# CPU.net
KiCad netlist of a schematic drawn in Altium Designer
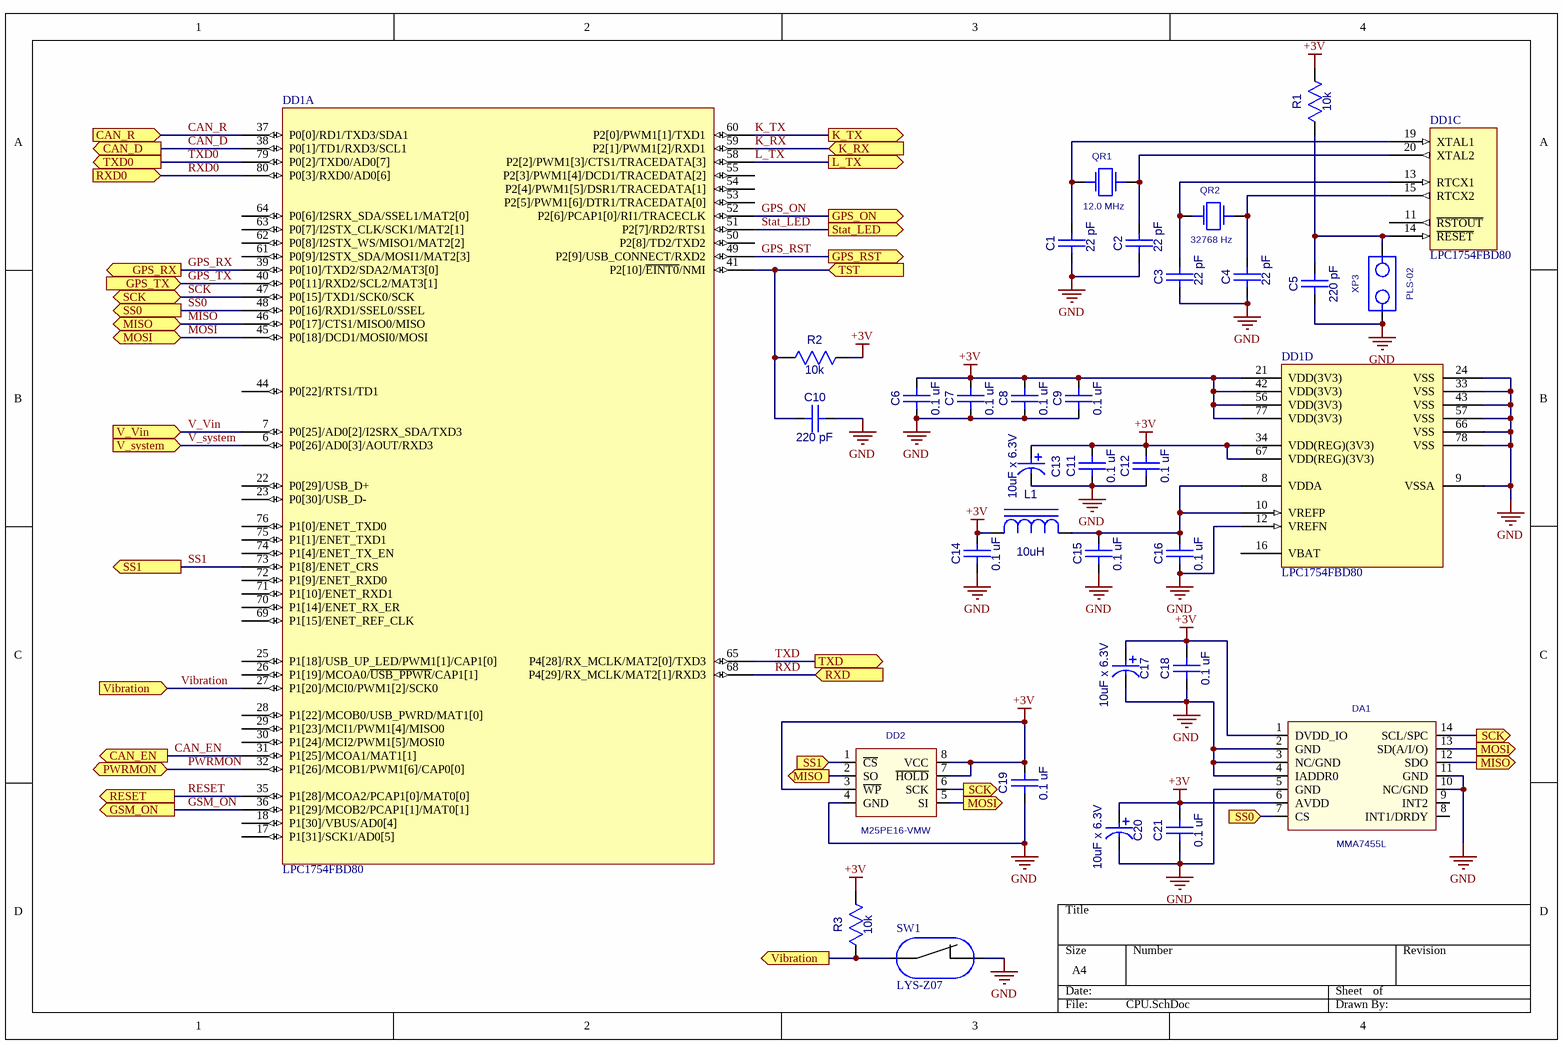
[diagram p0: CPU.SchDoc]

(export (version "E")
  (design (tool "Eeschema 10.0.6"))
  (components
    (comp (ref "C1")
      (value "22 pF")
      (footprint "CC0603-3M")
      (description "CC0603")
      (libsource (lib "gprs_modem") (part "CC0603"))
    )
    (comp (ref "C2")
      (value "22 pF")
      (footprint "CC0603-3M")
      (description "CC0603")
      (libsource (lib "gprs_modem") (part "CC0603"))
    )
    (comp (ref "C3")
      (value "22 pF")
      (footprint "CC0603-3M")
      (description "CC0603")
      (libsource (lib "gprs_modem") (part "CC0603"))
    )
    (comp (ref "C4")
      (value "22 pF")
      (footprint "CC0603-3M")
      (description "CC0603")
      (libsource (lib "gprs_modem") (part "CC0603"))
    )
    (comp (ref "C5")
      (value "220 pF")
      (footprint "CC0603-3M")
      (description "CC0603")
      (libsource (lib "gprs_modem") (part "CC0603"))
    )
    (comp (ref "C6")
      (value "0.1 uF")
      (footprint "CC0603-3M")
      (description "CC0603")
      (libsource (lib "gprs_modem") (part "CC0603"))
    )
    (comp (ref "C7")
      (value "0.1 uF")
      (footprint "CC0603-3M")
      (description "CC0603")
      (libsource (lib "gprs_modem") (part "CC0603"))
    )
    (comp (ref "C8")
      (value "0.1 uF")
      (footprint "CC0603-3M")
      (description "CC0603")
      (libsource (lib "gprs_modem") (part "CC0603"))
    )
    (comp (ref "C9")
      (value "0.1 uF")
      (footprint "CC0603-3M")
      (description "CC0603")
      (libsource (lib "gprs_modem") (part "CC0603"))
    )
    (comp (ref "C10")
      (value "220 pF")
      (footprint "CC0603-3M")
      (description "CC0603")
      (libsource (lib "gprs_modem") (part "CC0603"))
    )
    (comp (ref "C11")
      (value "0.1 uF")
      (footprint "CC0603-3M")
      (description "CC0603")
      (libsource (lib "gprs_modem") (part "CC0603"))
    )
    (comp (ref "C12")
      (value "0.1 uF")
      (footprint "CC0603-3M")
      (description "CC0603")
      (libsource (lib "gprs_modem") (part "CC0603"))
    )
    (comp (ref "C13")
      (value "10uF x 6.3V")
      (footprint "TAJ-A_M")
      (description "TAJ-A")
      (libsource (lib "Schetchik") (part "TAJ-A"))
    )
    (comp (ref "C14")
      (value "0.1 uF")
      (footprint "CC0603-3M")
      (description "CC0603")
      (libsource (lib "gprs_modem") (part "CC0603"))
    )
    (comp (ref "C15")
      (value "0.1 uF")
      (footprint "CC0603-3M")
      (description "CC0603")
      (libsource (lib "gprs_modem") (part "CC0603"))
    )
    (comp (ref "C16")
      (value "0.1 uF")
      (footprint "CC0603-3M")
      (description "CC0603")
      (libsource (lib "gprs_modem") (part "CC0603"))
    )
    (comp (ref "C17")
      (value "10uF x 6.3V")
      (footprint "TAJ-A_M")
      (description "TAJ-A")
      (libsource (lib "*") (part "TAJ-A"))
    )
    (comp (ref "C18")
      (value "0.1 uF")
      (footprint "CC0603-3M")
      (description "CC0603")
      (libsource (lib "*") (part "CC0603"))
    )
    (comp (ref "C19")
      (value "0.1 uF")
      (footprint "CC0603-3M")
      (description "CC0603")
      (libsource (lib "*") (part "CC0603"))
    )
    (comp (ref "C20")
      (value "10uF x 6.3V")
      (footprint "TAJ-A_M")
      (description "TAJ-A")
      (libsource (lib "*") (part "TAJ-A"))
    )
    (comp (ref "C21")
      (value "0.1 uF")
      (footprint "CC0603-3M")
      (description "CC0603")
      (libsource (lib "*") (part "CC0603"))
    )
    (comp (ref "DA1") (value "MMA7455L") (footprint "LGA-14") (libsource (lib "*") (part "MMA7455L")))
    (comp (ref "DD1")
      (value "LPC1754FBD80")
      (footprint "TQFP-80_0.5")
      (description "Cortex -M3 32-Bit Microcontroller, 128KB Flash, 64KB RAM, 800-Lead LQFP")
      (libsource (lib "gprs_modem") (part "LPC1754FBD80"))
    )
    (comp (ref "DD2")
      (value "M25PE16-VMW")
      (footprint "EIAJ_SO8")
      (description "S25FL016A0LMFI01")
      (libsource (lib "*") (part "S25FL016A0LMFI01"))
    )
    (comp (ref "L1")
      (value "10uH")
      (footprint "L0603")
      (description "L0603")
      (libsource (lib "gprs_modem") (part "L0603"))
    )
    (comp (ref "QR1")
      (value "12.0 MHz")
      (footprint "AC5032_2")
      (description "AC5032/2")
      (libsource (lib "gprs_modem") (part "AC5032_2"))
    )
    (comp (ref "QR2")
      (value "32768 Hz")
      (footprint "QR_32768")
      (description "CRYSTAL_32768 Hz")
      (libsource (lib "Schetchik") (part "CRYSTAL_32768"))
    )
    (comp (ref "R1")
      (value "10k")
      (footprint "RC0603-3M")
      (description "RC0603")
      (libsource (lib "gprs_modem") (part "RC0603"))
    )
    (comp (ref "R2")
      (value "10k")
      (footprint "RC0603-3M")
      (description "RC0603")
      (libsource (lib "gprs_modem") (part "RC0603"))
    )
    (comp (ref "R3")
      (value "10k")
      (footprint "RC0603-3M")
      (description "RC0603")
      (libsource (lib "gprs_modem") (part "RC0603"))
    )
    (comp (ref "SW1")
      (value "LYS-Z07")
      (footprint "LYS-Z07")
      (description "NC vibration sensor")
      (libsource (lib "gprs_modem") (part "LYS-Z07"))
    )
    (comp (ref "XP3") (value "PLS-02") (footprint "PIN2W") (libsource (lib "gprs_modem") (part "PLD-02")))
  )
  (nets
    (net (code "1") (name "+3V") (class "Default")
      (node (ref "C11") (pin "2") (pinfunction "B_2") (pintype "passive"))
      (node (ref "C12") (pin "2") (pinfunction "B_2") (pintype "passive"))
      (node (ref "C13") (pin "1") (pinfunction "A_1") (pintype "passive"))
      (node (ref "C14") (pin "2") (pinfunction "B_2") (pintype "passive"))
      (node (ref "C17") (pin "1") (pinfunction "A_1") (pintype "passive"))
      (node (ref "C18") (pin "2") (pinfunction "B_2") (pintype "passive"))
      (node (ref "C19") (pin "2") (pinfunction "B_2") (pintype "passive"))
      (node (ref "C20") (pin "1") (pinfunction "A_1") (pintype "passive"))
      (node (ref "C21") (pin "2") (pinfunction "B_2") (pintype "passive"))
      (node (ref "C6") (pin "2") (pinfunction "B_2") (pintype "passive"))
      (node (ref "C7") (pin "2") (pinfunction "B_2") (pintype "passive"))
      (node (ref "C8") (pin "2") (pinfunction "B_2") (pintype "passive"))
      (node (ref "C9") (pin "2") (pinfunction "B_2") (pintype "passive"))
      (node (ref "DA1") (pin "1") (pinfunction "DVDD_IO_1") (pintype "passive"))
      (node (ref "DA1") (pin "6") (pinfunction "AVDD_6") (pintype "passive"))
      (node (ref "DD1") (pin "21") (pinfunction "VDD(3V3)_21") (pintype "power_in"))
      (node (ref "DD1") (pin "34") (pinfunction "VDD(REG)(3V3)_34") (pintype "power_in"))
      (node (ref "DD1") (pin "42") (pinfunction "VDD(3V3)_42") (pintype "power_in"))
      (node (ref "DD1") (pin "56") (pinfunction "VDD(3V3)_56") (pintype "power_in"))
      (node (ref "DD1") (pin "67") (pinfunction "VDD(REG)(3V3)_67") (pintype "power_in"))
      (node (ref "DD1") (pin "77") (pinfunction "VDD(3V3)_77") (pintype "power_in"))
      (node (ref "DD2") (pin "3") (pinfunction "~{WP}_3") (pintype "passive"))
      (node (ref "DD2") (pin "7") (pinfunction "~{HOLD}_7") (pintype "passive"))
      (node (ref "DD2") (pin "8") (pinfunction "VCC_8") (pintype "passive"))
      (node (ref "L1") (pin "1") (pinfunction "A_1") (pintype "passive"))
      (node (ref "R1") (pin "2") (pinfunction "B_2") (pintype "passive"))
      (node (ref "R2") (pin "2") (pinfunction "B_2") (pintype "passive"))
      (node (ref "R3") (pin "2") (pinfunction "B_2") (pintype "passive"))
    )
    (net (code "2") (name "/CAN_D") (class "Default")
      (node (ref "DD1") (pin "38") (pinfunction "P0[1]/TD1/RXD3/SCL1_38") (pintype "bidirectional"))
    )
    (net (code "3") (name "/CAN_EN") (class "Default")
      (node (ref "DD1") (pin "31") (pinfunction "P1[25]/MCOA1/MAT1[1]_31") (pintype "bidirectional"))
    )
    (net (code "4") (name "/CAN_R") (class "Default")
      (node (ref "DD1") (pin "37") (pinfunction "P0[0]/RD1/TXD3/SDA1_37") (pintype "bidirectional"))
    )
    (net (code "5") (name "/GPS_ON") (class "Default")
      (node (ref "DD1") (pin "52") (pinfunction "P2[6]/PCAP1[0]/RI1/TRACECLK_52") (pintype "bidirectional"))
    )
    (net (code "6") (name "/GPS_RST") (class "Default")
      (node (ref "DD1") (pin "49") (pinfunction "P2[9]/USB_CONNECT/RXD2_49") (pintype "bidirectional"))
    )
    (net (code "7") (name "/GPS_RX") (class "Default")
      (node (ref "DD1") (pin "39") (pinfunction "P0[10]/TXD2/SDA2/MAT3[0]_39") (pintype "bidirectional"))
    )
    (net (code "8") (name "/GPS_TX") (class "Default")
      (node (ref "DD1") (pin "40") (pinfunction "P0[11]/RXD2/SCL2/MAT3[1]_40") (pintype "bidirectional"))
    )
    (net (code "9") (name "/GSM_ON") (class "Default")
      (node (ref "DD1") (pin "36") (pinfunction "P1[29]/MCOB2/PCAP1[1]/MAT0[1]_36") (pintype "bidirectional"))
    )
    (net (code "10") (name "/K_RX") (class "Default")
      (node (ref "DD1") (pin "59") (pinfunction "P2[1]/PWM1[2]/RXD1_59") (pintype "bidirectional"))
    )
    (net (code "11") (name "/K_TX") (class "Default")
      (node (ref "DD1") (pin "60") (pinfunction "P2[0]/PWM1[1]/TXD1_60") (pintype "bidirectional"))
    )
    (net (code "12") (name "/L_TX") (class "Default")
      (node (ref "DD1") (pin "58") (pinfunction "P2[2]/PWM1[3]/CTS1/TRACEDATA[3]_58") (pintype "bidirectional"))
    )
    (net (code "13") (name "/MISO") (class "Default")
      (node (ref "DA1") (pin "12") (pinfunction "SDO_12") (pintype "passive"))
      (node (ref "DD1") (pin "46") (pinfunction "P0[17]/CTS1/MISO0/MISO_46") (pintype "bidirectional"))
      (node (ref "DD2") (pin "2") (pinfunction "SO_2") (pintype "passive"))
    )
    (net (code "14") (name "/MOSI") (class "Default")
      (node (ref "DA1") (pin "13") (pinfunction "SD(A/I/O)_13") (pintype "passive"))
      (node (ref "DD1") (pin "45") (pinfunction "P0[18]/DCD1/MOSI0/MOSI_45") (pintype "bidirectional"))
      (node (ref "DD2") (pin "5") (pinfunction "SI_5") (pintype "passive"))
    )
    (net (code "15") (name "/PWRMON") (class "Default")
      (node (ref "DD1") (pin "32") (pinfunction "P1[26]/MCOB1/PWM1[6]/CAP0[0]_32") (pintype "bidirectional"))
    )
    (net (code "16") (name "/RESET") (class "Default")
      (node (ref "DD1") (pin "35") (pinfunction "P1[28]/MCOA2/PCAP1[0]/MAT0[0]_35") (pintype "bidirectional"))
    )
    (net (code "17") (name "/RXD") (class "Default")
      (node (ref "DD1") (pin "68") (pinfunction "P4[29]/RX_MCLK/MAT2[1]/RXD3_68") (pintype "bidirectional"))
    )
    (net (code "18") (name "/RXD0") (class "Default")
      (node (ref "DD1") (pin "80") (pinfunction "P0[3]/RXD0/AD0[6]_80") (pintype "bidirectional"))
    )
    (net (code "19") (name "/SCK") (class "Default")
      (node (ref "DA1") (pin "14") (pinfunction "SCL/SPC_14") (pintype "passive"))
      (node (ref "DD1") (pin "47") (pinfunction "P0[15]/TXD1/SCK0/SCK_47") (pintype "bidirectional"))
      (node (ref "DD2") (pin "6") (pinfunction "SCK_6") (pintype "passive"))
    )
    (net (code "20") (name "/SS0") (class "Default")
      (node (ref "DA1") (pin "7") (pinfunction "CS_7") (pintype "passive"))
      (node (ref "DD1") (pin "48") (pinfunction "P0[16]/RXD1/SSEL0/SSEL_48") (pintype "bidirectional"))
    )
    (net (code "21") (name "/SS1") (class "Default")
      (node (ref "DD1") (pin "73") (pinfunction "P1[8]/ENET_CRS_73") (pintype "bidirectional"))
      (node (ref "DD2") (pin "1") (pinfunction "~{CS}_1") (pintype "passive"))
    )
    (net (code "22") (name "/Stat_LED") (class "Default")
      (node (ref "DD1") (pin "51") (pinfunction "P2[7]/RD2/RTS1_51") (pintype "bidirectional"))
    )
    (net (code "23") (name "/TST") (class "Default")
      (node (ref "C10") (pin "1") (pinfunction "A_1") (pintype "passive"))
      (node (ref "DD1") (pin "41") (pinfunction "P2[10]/~{EINT0}/NMI_41") (pintype "bidirectional"))
      (node (ref "R2") (pin "1") (pinfunction "A_1") (pintype "passive"))
    )
    (net (code "24") (name "/TXD") (class "Default")
      (node (ref "DD1") (pin "65") (pinfunction "P4[28]/RX_MCLK/MAT2[0]/TXD3_65") (pintype "bidirectional"))
    )
    (net (code "25") (name "/TXD0") (class "Default")
      (node (ref "DD1") (pin "79") (pinfunction "P0[2]/TXD0/AD0[7]_79") (pintype "bidirectional"))
    )
    (net (code "26") (name "/V_Vin") (class "Default")
      (node (ref "DD1") (pin "7") (pinfunction "P0[25]/AD0[2]/I2SRX_SDA/TXD3_7") (pintype "bidirectional"))
    )
    (net (code "27") (name "/V_system") (class "Default")
      (node (ref "DD1") (pin "6") (pinfunction "P0[26]/AD0[3]/AOUT/RXD3_6") (pintype "bidirectional"))
    )
    (net (code "28") (name "/Vibration") (class "Default")
      (node (ref "DD1") (pin "27") (pinfunction "P1[20]/MCI0/PWM1[2]/SCK0_27") (pintype "bidirectional"))
      (node (ref "R3") (pin "1") (pinfunction "A_1") (pintype "passive"))
      (node (ref "SW1") (pin "1") (pinfunction "1_1") (pintype "passive"))
    )
    (net (code "29") (name "GND") (class "Default")
      (node (ref "C1") (pin "1") (pinfunction "A_1") (pintype "passive"))
      (node (ref "C10") (pin "2") (pinfunction "B_2") (pintype "passive"))
      (node (ref "C11") (pin "1") (pinfunction "A_1") (pintype "passive"))
      (node (ref "C12") (pin "1") (pinfunction "A_1") (pintype "passive"))
      (node (ref "C13") (pin "2") (pinfunction "B_2") (pintype "passive"))
      (node (ref "C14") (pin "1") (pinfunction "A_1") (pintype "passive"))
      (node (ref "C15") (pin "1") (pinfunction "A_1") (pintype "passive"))
      (node (ref "C16") (pin "1") (pinfunction "A_1") (pintype "passive"))
      (node (ref "C17") (pin "2") (pinfunction "B_2") (pintype "passive"))
      (node (ref "C18") (pin "1") (pinfunction "A_1") (pintype "passive"))
      (node (ref "C19") (pin "1") (pinfunction "A_1") (pintype "passive"))
      (node (ref "C2") (pin "1") (pinfunction "A_1") (pintype "passive"))
      (node (ref "C20") (pin "2") (pinfunction "B_2") (pintype "passive"))
      (node (ref "C21") (pin "1") (pinfunction "A_1") (pintype "passive"))
      (node (ref "C3") (pin "1") (pinfunction "A_1") (pintype "passive"))
      (node (ref "C4") (pin "1") (pinfunction "A_1") (pintype "passive"))
      (node (ref "C5") (pin "1") (pinfunction "A_1") (pintype "passive"))
      (node (ref "C6") (pin "1") (pinfunction "A_1") (pintype "passive"))
      (node (ref "C7") (pin "1") (pinfunction "A_1") (pintype "passive"))
      (node (ref "C8") (pin "1") (pinfunction "A_1") (pintype "passive"))
      (node (ref "C9") (pin "1") (pinfunction "A_1") (pintype "passive"))
      (node (ref "DA1") (pin "10") (pinfunction "NC/GND_10") (pintype "passive"))
      (node (ref "DA1") (pin "11") (pinfunction "GND_11") (pintype "passive"))
      (node (ref "DA1") (pin "2") (pinfunction "GND_2") (pintype "passive"))
      (node (ref "DA1") (pin "3") (pinfunction "NC/GND_3") (pintype "passive"))
      (node (ref "DA1") (pin "4") (pinfunction "IADDR0_4") (pintype "passive"))
      (node (ref "DA1") (pin "5") (pinfunction "GND_5") (pintype "passive"))
      (node (ref "DD1") (pin "12") (pinfunction "VREFN_12") (pintype "input"))
      (node (ref "DD1") (pin "24") (pinfunction "VSS_24") (pintype "power_in"))
      (node (ref "DD1") (pin "33") (pinfunction "VSS_33") (pintype "power_in"))
      (node (ref "DD1") (pin "43") (pinfunction "VSS_43") (pintype "power_in"))
      (node (ref "DD1") (pin "57") (pinfunction "VSS_57") (pintype "power_in"))
      (node (ref "DD1") (pin "66") (pinfunction "VSS_66") (pintype "power_in"))
      (node (ref "DD1") (pin "78") (pinfunction "VSS_78") (pintype "power_in"))
      (node (ref "DD1") (pin "9") (pinfunction "VSSA_9") (pintype "power_in"))
      (node (ref "DD2") (pin "4") (pinfunction "GND_4") (pintype "passive"))
      (node (ref "SW1") (pin "2") (pinfunction "2_2") (pintype "passive"))
      (node (ref "XP3") (pin "1") (pintype "passive"))
    )
    (net (code "30") (name "Net-(C1-B)") (class "Default")
      (node (ref "C1") (pin "2") (pinfunction "B_2") (pintype "passive"))
      (node (ref "DD1") (pin "19") (pinfunction "XTAL1_19") (pintype "input"))
      (node (ref "QR1") (pin "1") (pintype "passive"))
    )
    (net (code "31") (name "Net-(C2-B)") (class "Default")
      (node (ref "C2") (pin "2") (pinfunction "B_2") (pintype "passive"))
      (node (ref "DD1") (pin "20") (pinfunction "XTAL2_20") (pintype "output"))
      (node (ref "QR1") (pin "2") (pintype "passive"))
    )
    (net (code "32") (name "Net-(C3-B)") (class "Default")
      (node (ref "C3") (pin "2") (pinfunction "B_2") (pintype "passive"))
      (node (ref "DD1") (pin "13") (pinfunction "RTCX1_13") (pintype "input"))
      (node (ref "QR2") (pin "1") (pinfunction "X1_1") (pintype "passive"))
    )
    (net (code "33") (name "Net-(C4-B)") (class "Default")
      (node (ref "C4") (pin "2") (pinfunction "B_2") (pintype "passive"))
      (node (ref "DD1") (pin "15") (pinfunction "RTCX2_15") (pintype "output"))
      (node (ref "QR2") (pin "2") (pinfunction "X2_2") (pintype "passive"))
    )
    (net (code "34") (name "Net-(C5-B)") (class "Default")
      (node (ref "C5") (pin "2") (pinfunction "B_2") (pintype "passive"))
      (node (ref "DD1") (pin "14") (pinfunction "~{RESET}_14") (pintype "input"))
      (node (ref "R1") (pin "1") (pinfunction "A_1") (pintype "passive"))
      (node (ref "XP3") (pin "2") (pintype "passive"))
    )
    (net (code "35") (name "Net-(C15-B)") (class "Default")
      (node (ref "C15") (pin "2") (pinfunction "B_2") (pintype "passive"))
      (node (ref "C16") (pin "2") (pinfunction "B_2") (pintype "passive"))
      (node (ref "DD1") (pin "10") (pinfunction "VREFP_10") (pintype "input"))
      (node (ref "DD1") (pin "8") (pinfunction "VDDA_8") (pintype "power_in"))
      (node (ref "L1") (pin "2") (pinfunction "C_2") (pintype "passive"))
    )
    (net (code "36") (name "unconnected-(DA1-INT1{slash}DRDY-Pad8)") (class "Default")
      (node (ref "DA1") (pin "8") (pinfunction "INT1/DRDY_8") (pintype "passive"))
    )
    (net (code "37") (name "unconnected-(DA1-INT2-Pad9)") (class "Default")
      (node (ref "DA1") (pin "9") (pinfunction "INT2_9") (pintype "passive"))
    )
    (net (code "38") (name "unconnected-(DD1A-P0[6]{slash}I2SRX_SDA{slash}SSEL1{slash}MAT2[0]-Pad64)") (class "Default")
      (node (ref "DD1") (pin "64") (pinfunction "P0[6]/I2SRX_SDA/SSEL1/MAT2[0]_64") (pintype "bidirectional"))
    )
    (net (code "39") (name "unconnected-(DD1A-P0[7]{slash}I2STX_CLK{slash}SCK1{slash}MAT2[1]-Pad63)") (class "Default")
      (node (ref "DD1") (pin "63") (pinfunction "P0[7]/I2STX_CLK/SCK1/MAT2[1]_63") (pintype "bidirectional"))
    )
    (net (code "40") (name "unconnected-(DD1A-P0[8]{slash}I2STX_WS{slash}MISO1{slash}MAT2[2]-Pad62)") (class "Default")
      (node (ref "DD1") (pin "62") (pinfunction "P0[8]/I2STX_WS/MISO1/MAT2[2]_62") (pintype "bidirectional"))
    )
    (net (code "41") (name "unconnected-(DD1A-P0[9]{slash}I2STX_SDA{slash}MOSI1{slash}MAT2[3]-Pad61)") (class "Default")
      (node (ref "DD1") (pin "61") (pinfunction "P0[9]/I2STX_SDA/MOSI1/MAT2[3]_61") (pintype "bidirectional"))
    )
    (net (code "42") (name "unconnected-(DD1A-P0[22]{slash}RTS1{slash}TD1-Pad44)") (class "Default")
      (node (ref "DD1") (pin "44") (pinfunction "P0[22]/RTS1/TD1_44") (pintype "bidirectional"))
    )
    (net (code "43") (name "unconnected-(DD1A-P0[29]{slash}USB_D+-Pad22)") (class "Default")
      (node (ref "DD1") (pin "22") (pinfunction "P0[29]/USB_D+_22") (pintype "bidirectional"))
    )
    (net (code "44") (name "unconnected-(DD1A-P0[30]{slash}USB_D--Pad23)") (class "Default")
      (node (ref "DD1") (pin "23") (pinfunction "P0[30]/USB_D-_23") (pintype "bidirectional"))
    )
    (net (code "45") (name "unconnected-(DD1A-P1[0]{slash}ENET_TXD0-Pad76)") (class "Default")
      (node (ref "DD1") (pin "76") (pinfunction "P1[0]/ENET_TXD0_76") (pintype "bidirectional"))
    )
    (net (code "46") (name "unconnected-(DD1A-P1[1]{slash}ENET_TXD1-Pad75)") (class "Default")
      (node (ref "DD1") (pin "75") (pinfunction "P1[1]/ENET_TXD1_75") (pintype "bidirectional"))
    )
    (net (code "47") (name "unconnected-(DD1A-P1[4]{slash}ENET_TX_EN-Pad74)") (class "Default")
      (node (ref "DD1") (pin "74") (pinfunction "P1[4]/ENET_TX_EN_74") (pintype "bidirectional"))
    )
    (net (code "48") (name "unconnected-(DD1A-P1[9]{slash}ENET_RXD0-Pad72)") (class "Default")
      (node (ref "DD1") (pin "72") (pinfunction "P1[9]/ENET_RXD0_72") (pintype "bidirectional"))
    )
    (net (code "49") (name "unconnected-(DD1A-P1[10]{slash}ENET_RXD1-Pad71)") (class "Default")
      (node (ref "DD1") (pin "71") (pinfunction "P1[10]/ENET_RXD1_71") (pintype "bidirectional"))
    )
    (net (code "50") (name "unconnected-(DD1A-P1[14]{slash}ENET_RX_ER-Pad70)") (class "Default")
      (node (ref "DD1") (pin "70") (pinfunction "P1[14]/ENET_RX_ER_70") (pintype "bidirectional"))
    )
    (net (code "51") (name "unconnected-(DD1A-P1[15]{slash}ENET_REF_CLK-Pad69)") (class "Default")
      (node (ref "DD1") (pin "69") (pinfunction "P1[15]/ENET_REF_CLK_69") (pintype "bidirectional"))
    )
    (net (code "52") (name "unconnected-(DD1A-P1[18]{slash}USB_UP_LED{slash}PWM1[1]{slash}CAP1[0]-Pad25)") (class "Default")
      (node (ref "DD1") (pin "25") (pinfunction "P1[18]/USB_UP_LED/PWM1[1]/CAP1[0]_25") (pintype "bidirectional"))
    )
    (net (code "53") (name "unconnected-(DD1A-P1[19]{slash}MCOA0{slash}~{USB_PPWR}{slash}CAP1[1]-Pad26)") (class "Default")
      (node (ref "DD1") (pin "26") (pinfunction "P1[19]/MCOA0/~{USB_PPWR}/CAP1[1]_26") (pintype "bidirectional"))
    )
    (net (code "54") (name "unconnected-(DD1A-P1[22]{slash}MCOB0{slash}USB_PWRD{slash}MAT1[0]-Pad28)") (class "Default")
      (node (ref "DD1") (pin "28") (pinfunction "P1[22]/MCOB0/USB_PWRD/MAT1[0]_28") (pintype "bidirectional"))
    )
    (net (code "55") (name "unconnected-(DD1A-P1[23]{slash}MCI1{slash}PWM1[4]{slash}MISO0-Pad29)") (class "Default")
      (node (ref "DD1") (pin "29") (pinfunction "P1[23]/MCI1/PWM1[4]/MISO0_29") (pintype "bidirectional"))
    )
    (net (code "56") (name "unconnected-(DD1A-P1[24]{slash}MCI2{slash}PWM1[5]{slash}MOSI0-Pad30)") (class "Default")
      (node (ref "DD1") (pin "30") (pinfunction "P1[24]/MCI2/PWM1[5]/MOSI0_30") (pintype "bidirectional"))
    )
    (net (code "57") (name "unconnected-(DD1A-P1[30]{slash}VBUS{slash}AD0[4]-Pad18)") (class "Default")
      (node (ref "DD1") (pin "18") (pinfunction "P1[30]/VBUS/AD0[4]_18") (pintype "bidirectional"))
    )
    (net (code "58") (name "unconnected-(DD1A-P1[31]{slash}SCK1{slash}AD0[5]-Pad17)") (class "Default")
      (node (ref "DD1") (pin "17") (pinfunction "P1[31]/SCK1/AD0[5]_17") (pintype "bidirectional"))
    )
    (net (code "59") (name "unconnected-(DD1A-P2[3]{slash}PWM1[4]{slash}DCD1{slash}TRACEDATA[2]-Pad55)") (class "Default")
      (node (ref "DD1") (pin "55") (pinfunction "P2[3]/PWM1[4]/DCD1/TRACEDATA[2]_55") (pintype "bidirectional"))
    )
    (net (code "60") (name "unconnected-(DD1A-P2[4]{slash}PWM1[5]{slash}DSR1{slash}TRACEDATA[1]-Pad54)") (class "Default")
      (node (ref "DD1") (pin "54") (pinfunction "P2[4]/PWM1[5]/DSR1/TRACEDATA[1]_54") (pintype "bidirectional"))
    )
    (net (code "61") (name "unconnected-(DD1A-P2[5]{slash}PWM1[6]{slash}DTR1{slash}TRACEDATA[0]-Pad53)") (class "Default")
      (node (ref "DD1") (pin "53") (pinfunction "P2[5]/PWM1[6]/DTR1/TRACEDATA[0]_53") (pintype "bidirectional"))
    )
    (net (code "62") (name "unconnected-(DD1A-P2[8]{slash}TD2{slash}TXD2-Pad50)") (class "Default")
      (node (ref "DD1") (pin "50") (pinfunction "P2[8]/TD2/TXD2_50") (pintype "bidirectional"))
    )
    (net (code "63") (name "unconnected-(DD1C-~{RSTOUT}-Pad11)") (class "Default")
      (node (ref "DD1") (pin "11") (pinfunction "~{RSTOUT}_11") (pintype "output"))
    )
    (net (code "64") (name "unconnected-(DD1D-VBAT-Pad16)") (class "Default")
      (node (ref "DD1") (pin "16") (pinfunction "VBAT_16") (pintype "power_in"))
    )
  )
)
